# RFID_Lock_System.net
KiCad netlist of a schematic drawn in EAGLE
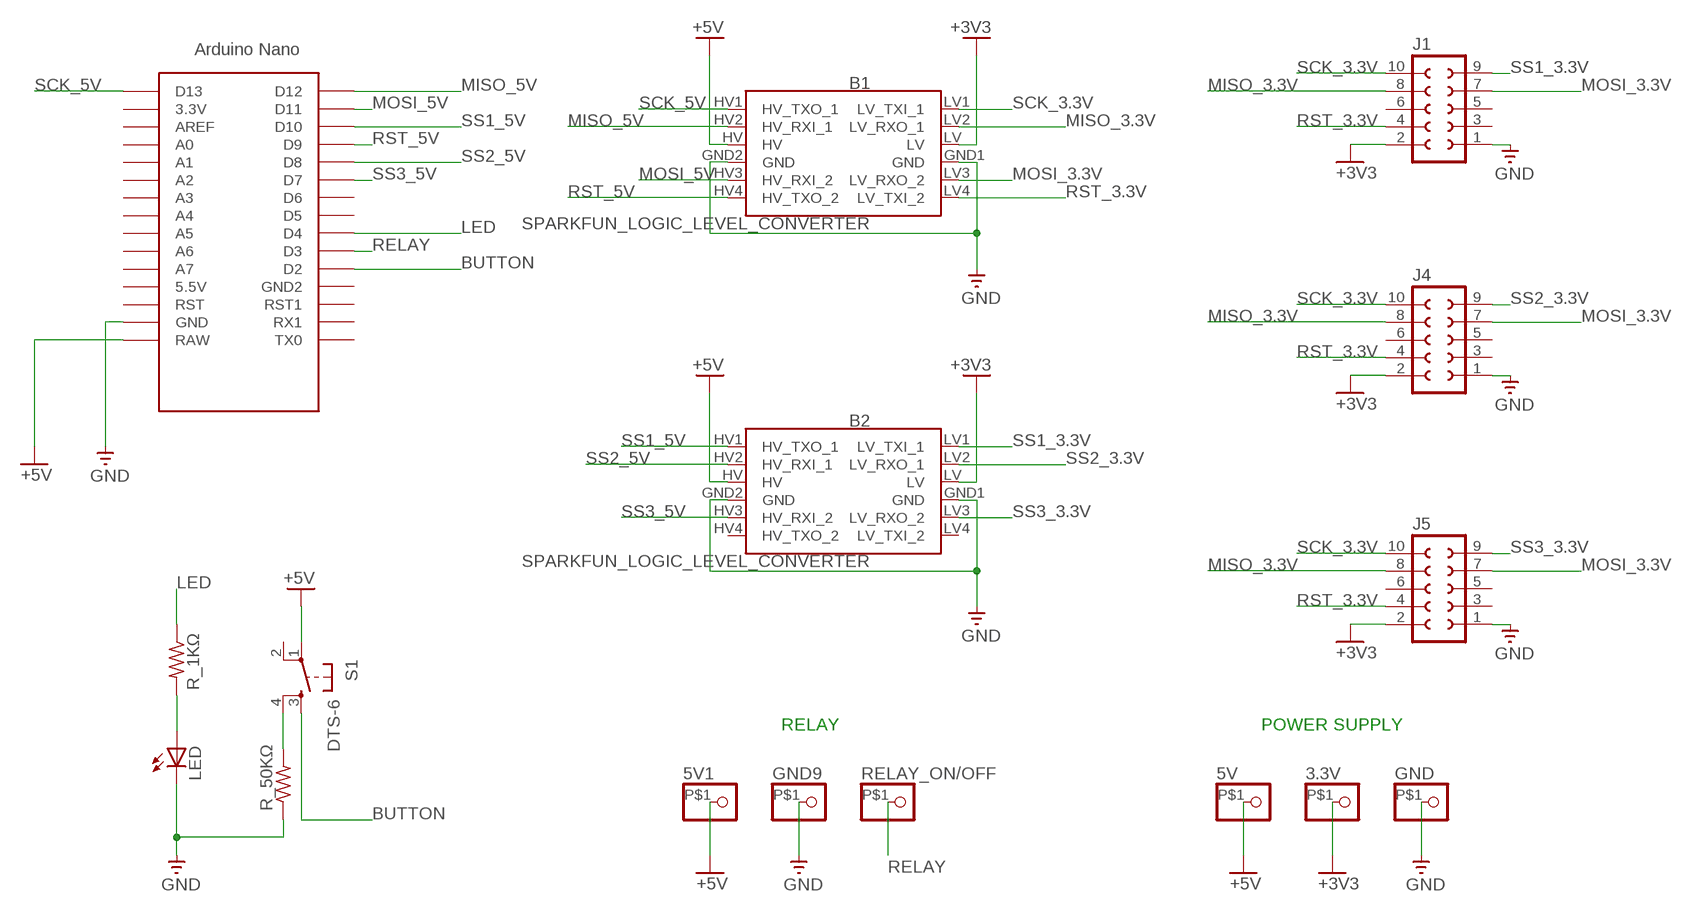
[diagram p0: schematic, sheet 1]

(export (version "E")
  (design (tool "Eeschema 10.0.6"))
  (components
    (comp (ref "3.3V")
      (value "PINHD-1X1-BIGPOGO")
      (footprint "eagle-import:1X1-BIGPOGO")
      (libsource (lib "eagle-import") (part "PINHD-1X1-BIGPOGO"))
    )
    (comp (ref "5V")
      (value "PINHD-1X1-BIGPOGO")
      (footprint "eagle-import:1X1-BIGPOGO")
      (libsource (lib "eagle-import") (part "PINHD-1X1-BIGPOGO"))
    )
    (comp (ref "5V1")
      (value "PINHD-1X1-BIGPOGO")
      (footprint "eagle-import:1X1-BIGPOGO")
      (libsource (lib "eagle-import") (part "PINHD-1X1-BIGPOGO"))
    )
    (comp (ref "B1")
      (value "SPARKFUN_LOGIC_LEVEL_CONVERTER")
      (footprint "eagle-import:SPARKFUN_LOGIC_LEVEL_CONVERTER")
      (libsource (lib "eagle-import") (part "SPARKFUN_LOGIC_LEVEL_CONVERTER"))
    )
    (comp (ref "B2")
      (value "SPARKFUN_LOGIC_LEVEL_CONVERTER")
      (footprint "eagle-import:SPARKFUN_LOGIC_LEVEL_CONVERTER")
      (libsource (lib "eagle-import") (part "SPARKFUN_LOGIC_LEVEL_CONVERTER"))
    )
    (comp (ref "GND")
      (value "PINHD-1X1-BIGPOGO")
      (footprint "eagle-import:1X1-BIGPOGO")
      (libsource (lib "eagle-import") (part "PINHD-1X1-BIGPOGO"))
    )
    (comp (ref "GND9")
      (value "PINHD-1X1-BIGPOGO")
      (footprint "eagle-import:1X1-BIGPOGO")
      (libsource (lib "eagle-import") (part "PINHD-1X1-BIGPOGO"))
    )
    (comp (ref "J1")
      (value "SOCKET-10V")
      (footprint "eagle-import:S10V")
      (libsource (lib "eagle-import") (part "SOCKET-10V"))
    )
    (comp (ref "J4")
      (value "SOCKET-10V")
      (footprint "eagle-import:S10V")
      (libsource (lib "eagle-import") (part "SOCKET-10V"))
    )
    (comp (ref "J5")
      (value "SOCKET-10V")
      (footprint "eagle-import:S10V")
      (libsource (lib "eagle-import") (part "SOCKET-10V"))
    )
    (comp (ref "LED")
      (value "LED5MM")
      (footprint "eagle-import:LED5MM")
      (libsource (lib "eagle-import") (part "LED5MM"))
    )
    (comp (ref "RELAY_ON/OFF")
      (value "PINHD-1X1-BIGPOGO")
      (footprint "eagle-import:1X1-BIGPOGO")
      (libsource (lib "eagle-import") (part "PINHD-1X1-BIGPOGO"))
    )
    (comp (ref "R_1KΩ")
      (value "R-US_0204/7")
      (footprint "eagle-import:0204_7")
      (libsource (lib "eagle-import") (part "R-US_0204/7"))
    )
    (comp (ref "R_50KΩ")
      (value "R-US_0204/7")
      (footprint "eagle-import:0204_7")
      (libsource (lib "eagle-import") (part "R-US_0204/7"))
    )
    (comp (ref "S1")
      (value "DTS-6")
      (footprint "eagle-import:DTS-6")
      (fields (field (name "MPN") "MC32829"))
      (libsource (lib "eagle-import") (part "DTS-6"))
    )
    (comp (ref "U$1")
      (value "NANO")
      (footprint "eagle-import:NANO")
      (libsource (lib "eagle-import") (part "NANO"))
    )
  )
  (nets
    (net (code "1") (name "+3V3") (class "Default")
      (node (ref "3.3V") (pin "P$1") (pinfunction "1_P$1") (pintype "passive"))
      (node (ref "B1") (pin "LV") (pinfunction "LV_LV") (pintype "power_in"))
      (node (ref "B2") (pin "LV") (pinfunction "LV_LV") (pintype "power_in"))
      (node (ref "J1") (pin "2") (pinfunction "2_2") (pintype "passive"))
      (node (ref "J4") (pin "2") (pinfunction "2_2") (pintype "passive"))
      (node (ref "J5") (pin "2") (pinfunction "2_2") (pintype "passive"))
    )
    (net (code "2") (name "+5V") (class "Default")
      (node (ref "5V") (pin "P$1") (pinfunction "1_P$1") (pintype "passive"))
      (node (ref "5V1") (pin "P$1") (pinfunction "1_P$1") (pintype "passive"))
      (node (ref "B1") (pin "HV") (pinfunction "HV_HV") (pintype "power_in"))
      (node (ref "B2") (pin "HV") (pinfunction "HV_HV") (pintype "power_in"))
      (node (ref "S1") (pin "1") (pinfunction "1_1") (pintype "passive"))
      (node (ref "U$1") (pin "RAW") (pinfunction "RAW_RAW") (pintype "bidirectional"))
    )
    (net (code "3") (name "/BUTTON") (class "Default")
      (node (ref "S1") (pin "3") (pinfunction "3_3") (pintype "passive"))
      (node (ref "U$1") (pin "D2") (pinfunction "D2_D2") (pintype "bidirectional"))
    )
    (net (code "4") (name "/LED") (class "Default")
      (node (ref "R_1KΩ") (pin "1") (pinfunction "1_1") (pintype "passive"))
      (node (ref "U$1") (pin "D4") (pinfunction "D4_D4") (pintype "bidirectional"))
    )
    (net (code "5") (name "/MISO_3.3V") (class "Default")
      (node (ref "B1") (pin "LV2") (pinfunction "LV_RXO_1_LV2") (pintype "bidirectional"))
      (node (ref "J1") (pin "8") (pinfunction "8_8") (pintype "passive"))
      (node (ref "J4") (pin "8") (pinfunction "8_8") (pintype "passive"))
      (node (ref "J5") (pin "8") (pinfunction "8_8") (pintype "passive"))
    )
    (net (code "6") (name "/MISO_5V") (class "Default")
      (node (ref "B1") (pin "HV2") (pinfunction "HV_RXI_1_HV2") (pintype "bidirectional"))
      (node (ref "U$1") (pin "D12") (pinfunction "D12_D12") (pintype "bidirectional"))
    )
    (net (code "7") (name "/MOSI_3.3V") (class "Default")
      (node (ref "B1") (pin "LV3") (pinfunction "LV_RXO_2_LV3") (pintype "bidirectional"))
      (node (ref "J1") (pin "7") (pinfunction "7_7") (pintype "passive"))
      (node (ref "J4") (pin "7") (pinfunction "7_7") (pintype "passive"))
      (node (ref "J5") (pin "7") (pinfunction "7_7") (pintype "passive"))
    )
    (net (code "8") (name "/MOSI_5V") (class "Default")
      (node (ref "B1") (pin "HV3") (pinfunction "HV_RXI_2_HV3") (pintype "bidirectional"))
      (node (ref "U$1") (pin "D11") (pinfunction "D11_D11") (pintype "bidirectional"))
    )
    (net (code "9") (name "/RELAY") (class "Default")
      (node (ref "RELAY_ON/OFF") (pin "P$1") (pinfunction "1_P$1") (pintype "passive"))
      (node (ref "U$1") (pin "D3") (pinfunction "D3_D3") (pintype "bidirectional"))
    )
    (net (code "10") (name "/RST_3.3V") (class "Default")
      (node (ref "B1") (pin "LV4") (pinfunction "LV_TXI_2_LV4") (pintype "bidirectional"))
      (node (ref "J1") (pin "4") (pinfunction "4_4") (pintype "passive"))
      (node (ref "J4") (pin "4") (pinfunction "4_4") (pintype "passive"))
      (node (ref "J5") (pin "4") (pinfunction "4_4") (pintype "passive"))
    )
    (net (code "11") (name "/RST_5V") (class "Default")
      (node (ref "B1") (pin "HV4") (pinfunction "HV_TXO_2_HV4") (pintype "bidirectional"))
      (node (ref "U$1") (pin "D9") (pinfunction "D9_D9") (pintype "bidirectional"))
    )
    (net (code "12") (name "/SCK_3.3V") (class "Default")
      (node (ref "B1") (pin "LV1") (pinfunction "LV_TXI_1_LV1") (pintype "bidirectional"))
      (node (ref "J1") (pin "10") (pinfunction "10_10") (pintype "passive"))
      (node (ref "J4") (pin "10") (pinfunction "10_10") (pintype "passive"))
      (node (ref "J5") (pin "10") (pinfunction "10_10") (pintype "passive"))
    )
    (net (code "13") (name "/SCK_5V") (class "Default")
      (node (ref "B1") (pin "HV1") (pinfunction "HV_TXO_1_HV1") (pintype "bidirectional"))
      (node (ref "U$1") (pin "D13") (pinfunction "D13_D13") (pintype "bidirectional"))
    )
    (net (code "14") (name "/SS1_3.3V") (class "Default")
      (node (ref "B2") (pin "LV1") (pinfunction "LV_TXI_1_LV1") (pintype "bidirectional"))
      (node (ref "J1") (pin "9") (pinfunction "9_9") (pintype "passive"))
    )
    (net (code "15") (name "/SS1_5V") (class "Default")
      (node (ref "B2") (pin "HV1") (pinfunction "HV_TXO_1_HV1") (pintype "bidirectional"))
      (node (ref "U$1") (pin "D10") (pinfunction "D10_D10") (pintype "bidirectional"))
    )
    (net (code "16") (name "/SS2_3.3V") (class "Default")
      (node (ref "B2") (pin "LV2") (pinfunction "LV_RXO_1_LV2") (pintype "bidirectional"))
      (node (ref "J4") (pin "9") (pinfunction "9_9") (pintype "passive"))
    )
    (net (code "17") (name "/SS2_5V") (class "Default")
      (node (ref "B2") (pin "HV2") (pinfunction "HV_RXI_1_HV2") (pintype "bidirectional"))
      (node (ref "U$1") (pin "D8") (pinfunction "D8_D8") (pintype "bidirectional"))
    )
    (net (code "18") (name "/SS3_3.3V") (class "Default")
      (node (ref "B2") (pin "LV3") (pinfunction "LV_RXO_2_LV3") (pintype "bidirectional"))
      (node (ref "J5") (pin "9") (pinfunction "9_9") (pintype "passive"))
    )
    (net (code "19") (name "/SS3_5V") (class "Default")
      (node (ref "B2") (pin "HV3") (pinfunction "HV_RXI_2_HV3") (pintype "bidirectional"))
      (node (ref "U$1") (pin "D7") (pinfunction "D7_D7") (pintype "bidirectional"))
    )
    (net (code "20") (name "GND") (class "Default")
      (node (ref "B1") (pin "GND1") (pinfunction "GND_GND1") (pintype "power_in"))
      (node (ref "B1") (pin "GND2") (pinfunction "GND_GND2") (pintype "power_in"))
      (node (ref "B2") (pin "GND1") (pinfunction "GND_GND1") (pintype "power_in"))
      (node (ref "B2") (pin "GND2") (pinfunction "GND_GND2") (pintype "power_in"))
      (node (ref "GND") (pin "P$1") (pinfunction "1_P$1") (pintype "passive"))
      (node (ref "GND9") (pin "P$1") (pinfunction "1_P$1") (pintype "passive"))
      (node (ref "J1") (pin "1") (pinfunction "1_1") (pintype "passive"))
      (node (ref "J4") (pin "1") (pinfunction "1_1") (pintype "passive"))
      (node (ref "J5") (pin "1") (pinfunction "1_1") (pintype "passive"))
      (node (ref "LED") (pin "K") (pinfunction "C_K") (pintype "passive"))
      (node (ref "R_50KΩ") (pin "1") (pinfunction "1_1") (pintype "passive"))
      (node (ref "U$1") (pin "GND") (pinfunction "GND_GND") (pintype "bidirectional"))
    )
    (net (code "21") (name "Net-(LED-PadA)") (class "Default")
      (node (ref "LED") (pin "A") (pinfunction "A_A") (pintype "passive"))
      (node (ref "R_1KΩ") (pin "2") (pinfunction "2_2") (pintype "passive"))
    )
    (net (code "22") (name "Net-(R_50KΩ-Pad2)") (class "Default")
      (node (ref "R_50KΩ") (pin "2") (pinfunction "2_2") (pintype "passive"))
      (node (ref "S1") (pin "4") (pinfunction "4_4") (pintype "passive"))
    )
    (net (code "23") (name "unconnected-(B2-HV_TXO_2-PadHV4)") (class "Default")
      (node (ref "B2") (pin "HV4") (pinfunction "HV_TXO_2_HV4") (pintype "bidirectional"))
    )
    (net (code "24") (name "unconnected-(B2-LV_TXI_2-PadLV4)") (class "Default")
      (node (ref "B2") (pin "LV4") (pinfunction "LV_TXI_2_LV4") (pintype "bidirectional"))
    )
    (net (code "25") (name "unconnected-(J1-Pad3)") (class "Default")
      (node (ref "J1") (pin "3") (pinfunction "3_3") (pintype "passive"))
    )
    (net (code "26") (name "unconnected-(J1-Pad5)") (class "Default")
      (node (ref "J1") (pin "5") (pinfunction "5_5") (pintype "passive"))
    )
    (net (code "27") (name "unconnected-(J1-Pad6)") (class "Default")
      (node (ref "J1") (pin "6") (pinfunction "6_6") (pintype "passive"))
    )
    (net (code "28") (name "unconnected-(J4-Pad3)") (class "Default")
      (node (ref "J4") (pin "3") (pinfunction "3_3") (pintype "passive"))
    )
    (net (code "29") (name "unconnected-(J4-Pad5)") (class "Default")
      (node (ref "J4") (pin "5") (pinfunction "5_5") (pintype "passive"))
    )
    (net (code "30") (name "unconnected-(J4-Pad6)") (class "Default")
      (node (ref "J4") (pin "6") (pinfunction "6_6") (pintype "passive"))
    )
    (net (code "31") (name "unconnected-(J5-Pad3)") (class "Default")
      (node (ref "J5") (pin "3") (pinfunction "3_3") (pintype "passive"))
    )
    (net (code "32") (name "unconnected-(J5-Pad5)") (class "Default")
      (node (ref "J5") (pin "5") (pinfunction "5_5") (pintype "passive"))
    )
    (net (code "33") (name "unconnected-(J5-Pad6)") (class "Default")
      (node (ref "J5") (pin "6") (pinfunction "6_6") (pintype "passive"))
    )
    (net (code "34") (name "unconnected-(S1-Pad2)") (class "Default")
      (node (ref "S1") (pin "2") (pinfunction "2_2") (pintype "passive"))
    )
    (net (code "35") (name "unconnected-(U$1-5.5V-Pad5V)") (class "Default")
      (node (ref "U$1") (pin "5V") (pinfunction "5.5V_5V") (pintype "bidirectional"))
    )
    (net (code "36") (name "unconnected-(U$1-GND2-PadGND1)") (class "Default")
      (node (ref "U$1") (pin "GND1") (pinfunction "GND2_GND1") (pintype "bidirectional"))
    )
    (net (code "37") (name "unconnected-(U$1-Pad3.3V)") (class "Default")
      (node (ref "U$1") (pin "3.3V") (pinfunction "3.3V_3.3V") (pintype "bidirectional"))
    )
    (net (code "38") (name "unconnected-(U$1-PadA0)") (class "Default")
      (node (ref "U$1") (pin "A0") (pinfunction "A0_A0") (pintype "bidirectional"))
    )
    (net (code "39") (name "unconnected-(U$1-PadA1)") (class "Default")
      (node (ref "U$1") (pin "A1") (pinfunction "A1_A1") (pintype "bidirectional"))
    )
    (net (code "40") (name "unconnected-(U$1-PadA2)") (class "Default")
      (node (ref "U$1") (pin "A2") (pinfunction "A2_A2") (pintype "bidirectional"))
    )
    (net (code "41") (name "unconnected-(U$1-PadA3)") (class "Default")
      (node (ref "U$1") (pin "A3") (pinfunction "A3_A3") (pintype "bidirectional"))
    )
    (net (code "42") (name "unconnected-(U$1-PadA4)") (class "Default")
      (node (ref "U$1") (pin "A4") (pinfunction "A4_A4") (pintype "bidirectional"))
    )
    (net (code "43") (name "unconnected-(U$1-PadA5)") (class "Default")
      (node (ref "U$1") (pin "A5") (pinfunction "A5_A5") (pintype "bidirectional"))
    )
    (net (code "44") (name "unconnected-(U$1-PadA6)") (class "Default")
      (node (ref "U$1") (pin "A6") (pinfunction "A6_A6") (pintype "bidirectional"))
    )
    (net (code "45") (name "unconnected-(U$1-PadA7)") (class "Default")
      (node (ref "U$1") (pin "A7") (pinfunction "A7_A7") (pintype "bidirectional"))
    )
    (net (code "46") (name "unconnected-(U$1-PadAREF)") (class "Default")
      (node (ref "U$1") (pin "AREF") (pinfunction "AREF_AREF") (pintype "bidirectional"))
    )
    (net (code "47") (name "unconnected-(U$1-PadD5)") (class "Default")
      (node (ref "U$1") (pin "D5") (pinfunction "D5_D5") (pintype "bidirectional"))
    )
    (net (code "48") (name "unconnected-(U$1-PadD6)") (class "Default")
      (node (ref "U$1") (pin "D6") (pinfunction "D6_D6") (pintype "bidirectional"))
    )
    (net (code "49") (name "unconnected-(U$1-PadICSP1)") (class "Default")
      (node (ref "U$1") (pin "ICSP1") (pinfunction "ICSP1_ICSP1") (pintype "bidirectional"))
    )
    (net (code "50") (name "unconnected-(U$1-PadICSP2)") (class "Default")
      (node (ref "U$1") (pin "ICSP2") (pinfunction "ICSP2_ICSP2") (pintype "bidirectional"))
    )
    (net (code "51") (name "unconnected-(U$1-PadICSP3)") (class "Default")
      (node (ref "U$1") (pin "ICSP3") (pinfunction "ICSP3_ICSP3") (pintype "bidirectional"))
    )
    (net (code "52") (name "unconnected-(U$1-PadICSP4)") (class "Default")
      (node (ref "U$1") (pin "ICSP4") (pinfunction "ICSP4_ICSP4") (pintype "bidirectional"))
    )
    (net (code "53") (name "unconnected-(U$1-PadICSP5)") (class "Default")
      (node (ref "U$1") (pin "ICSP5") (pinfunction "ICSP5_ICSP5") (pintype "bidirectional"))
    )
    (net (code "54") (name "unconnected-(U$1-PadICSP6)") (class "Default")
      (node (ref "U$1") (pin "ICSP6") (pinfunction "ICSP6_ICSP6") (pintype "bidirectional"))
    )
    (net (code "55") (name "unconnected-(U$1-PadRST)") (class "Default")
      (node (ref "U$1") (pin "RST") (pinfunction "RST_RST") (pintype "bidirectional"))
    )
    (net (code "56") (name "unconnected-(U$1-PadRST1)") (class "Default")
      (node (ref "U$1") (pin "RST1") (pinfunction "RST1_RST1") (pintype "bidirectional"))
    )
    (net (code "57") (name "unconnected-(U$1-PadRX1)") (class "Default")
      (node (ref "U$1") (pin "RX1") (pinfunction "RX1_RX1") (pintype "bidirectional"))
    )
    (net (code "58") (name "unconnected-(U$1-PadTX0)") (class "Default")
      (node (ref "U$1") (pin "TX0") (pinfunction "TX0_TX0") (pintype "bidirectional"))
    )
  )
)
